# TE0888.net
KiCad netlist of a schematic drawn in Altium Designer
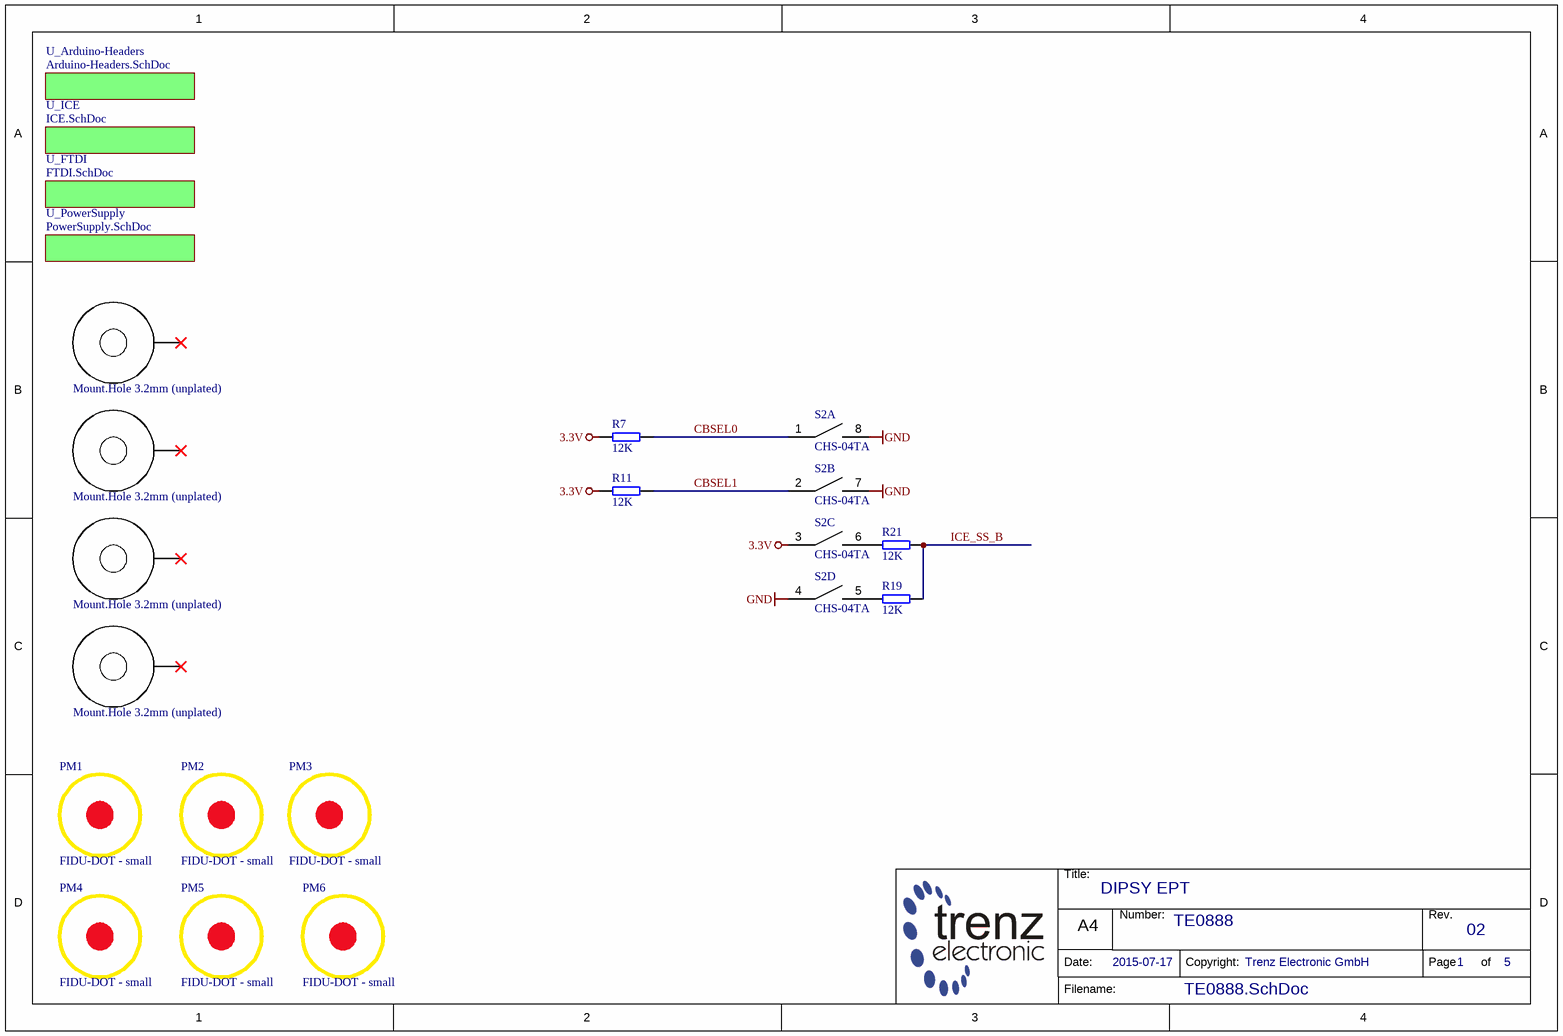
[diagram p0: TE0888.SchDoc]

(export (version "E")
  (design (tool "Eeschema 10.0.6"))
  (components
    (comp (ref "H1")
      (value "Mount.Hole 3.2mm (unplated)")
      (footprint "MHole3_2mm-UNPLATED")
      (libsource (lib "TE") (part "MHole"))
    )
    (comp (ref "H2")
      (value "Mount.Hole 3.2mm (unplated)")
      (footprint "MHole3_2mm-UNPLATED")
      (libsource (lib "TE") (part "MHole"))
    )
    (comp (ref "H3")
      (value "Mount.Hole 3.2mm (unplated)")
      (footprint "MHole3_2mm-UNPLATED")
      (libsource (lib "TE") (part "MHole"))
    )
    (comp (ref "H4")
      (value "Mount.Hole 3.2mm (unplated)")
      (footprint "MHole3_2mm-UNPLATED")
      (libsource (lib "TE") (part "MHole"))
    )
    (comp (ref "PM1")
      (value "FIDU-DOT - small")
      (footprint "FIDU-DOT - small")
      (description "FIDU-DOT - SMALL")
      (libsource (lib "TE") (part "FIDU-DOT - small"))
    )
    (comp (ref "PM2")
      (value "FIDU-DOT - small")
      (footprint "FIDU-DOT - small")
      (description "FIDU-DOT - SMALL")
      (libsource (lib "TE") (part "FIDU-DOT - small"))
    )
    (comp (ref "PM3")
      (value "FIDU-DOT - small")
      (footprint "FIDU-DOT - small")
      (description "FIDU-DOT - SMALL")
      (libsource (lib "TE") (part "FIDU-DOT - small"))
    )
    (comp (ref "PM4")
      (value "FIDU-DOT - small")
      (footprint "FIDU-DOT - small")
      (description "FIDU-DOT - SMALL")
      (libsource (lib "TE") (part "FIDU-DOT - small"))
    )
    (comp (ref "PM5")
      (value "FIDU-DOT - small")
      (footprint "FIDU-DOT - small")
      (description "FIDU-DOT - SMALL")
      (libsource (lib "TE") (part "FIDU-DOT - small"))
    )
    (comp (ref "PM6")
      (value "FIDU-DOT - small")
      (footprint "FIDU-DOT - small")
      (description "FIDU-DOT - SMALL")
      (libsource (lib "TE") (part "FIDU-DOT - small"))
    )
    (comp (ref "R7")
      (value "12K")
      (footprint "RESC1005X40N")
      (description "WID SMD 12K 1% 0,063W")
      (libsource (lib "TE") (part "RES"))
    )
    (comp (ref "R11")
      (value "12K")
      (footprint "RESC1005X40N")
      (description "WID SMD 12K 1% 0,063W")
      (libsource (lib "TE") (part "RES"))
    )
    (comp (ref "R19")
      (value "12K")
      (footprint "RESC1005X40N")
      (description "WID SMD 12K 1% 0,063W")
      (libsource (lib "TE") (part "RES"))
    )
    (comp (ref "R21")
      (value "12K")
      (footprint "RESC1005X40N")
      (description "WID SMD 12K 1% 0,063W")
      (libsource (lib "TE") (part "RES"))
    )
    (comp (ref "S2")
      (value "CHS-04TA")
      (footprint "CHS-04TA")
      (description "DIP Schalter 4 fach 1,27mm SMD")
      (libsource (lib "TE") (part "CHS-04TA"))
    )
  )
  (nets
    (net (code "1") (name "/CBSEL0") (class "Default")
      (node (ref "R7") (pin "1") (pinfunction "1_1") (pintype "passive"))
      (node (ref "S2") (pin "1") (pinfunction "1_1") (pintype "passive"))
    )
    (net (code "2") (name "/CBSEL1") (class "Default")
      (node (ref "R11") (pin "1") (pinfunction "1_1") (pintype "passive"))
      (node (ref "S2") (pin "2") (pinfunction "2_2") (pintype "passive"))
    )
    (net (code "3") (name "/ICE_SS_B") (class "Default")
      (node (ref "R19") (pin "1") (pinfunction "1_1") (pintype "passive"))
      (node (ref "R21") (pin "1") (pinfunction "1_1") (pintype "passive"))
    )
    (net (code "4") (name "3.3V") (class "Default")
      (node (ref "R11") (pin "2") (pinfunction "2_2") (pintype "passive"))
      (node (ref "R7") (pin "2") (pinfunction "2_2") (pintype "passive"))
      (node (ref "S2") (pin "3") (pinfunction "3_3") (pintype "passive"))
    )
    (net (code "5") (name "GND") (class "Default")
      (node (ref "S2") (pin "4") (pinfunction "4_4") (pintype "passive"))
      (node (ref "S2") (pin "7") (pinfunction "7_7") (pintype "passive"))
      (node (ref "S2") (pin "8") (pinfunction "8_8") (pintype "passive"))
    )
    (net (code "6") (name "Net-(R19-Pad2)") (class "Default")
      (node (ref "R19") (pin "2") (pinfunction "2_2") (pintype "passive"))
      (node (ref "S2") (pin "5") (pinfunction "5_5") (pintype "passive"))
    )
    (net (code "7") (name "Net-(R21-Pad2)") (class "Default")
      (node (ref "R21") (pin "2") (pinfunction "2_2") (pintype "passive"))
      (node (ref "S2") (pin "6") (pinfunction "6_6") (pintype "passive"))
    )
    (net (code "8") (name "unconnected-(H1-Pad1)") (class "Default")
      (node (ref "H1") (pin "1") (pinfunction "1_1") (pintype "passive+no_connect"))
    )
    (net (code "9") (name "unconnected-(H2-Pad1)") (class "Default")
      (node (ref "H2") (pin "1") (pinfunction "1_1") (pintype "passive+no_connect"))
    )
    (net (code "10") (name "unconnected-(H3-Pad1)") (class "Default")
      (node (ref "H3") (pin "1") (pinfunction "1_1") (pintype "passive+no_connect"))
    )
    (net (code "11") (name "unconnected-(H4-Pad1)") (class "Default")
      (node (ref "H4") (pin "1") (pinfunction "1_1") (pintype "passive+no_connect"))
    )
  )
)
